# klbr4breakout.net
KiCad netlist of a schematic drawn in EAGLE
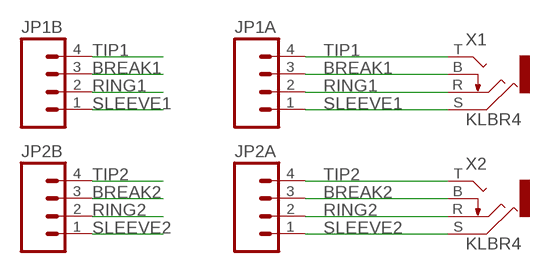
[diagram p0: schematic, sheet 1]

(export (version "E")
  (design (tool "Eeschema 10.0.6"))
  (components
    (comp (ref "JP1A")
      (value "M04PTH")
      (footprint "eagle-import:1X04")
      (libsource (lib "eagle-import") (part "M04PTH"))
    )
    (comp (ref "JP1B")
      (value "M04PTH")
      (footprint "eagle-import:1X04")
      (libsource (lib "eagle-import") (part "M04PTH"))
    )
    (comp (ref "JP2A")
      (value "M04PTH")
      (footprint "eagle-import:1X04")
      (libsource (lib "eagle-import") (part "M04PTH"))
    )
    (comp (ref "JP2B")
      (value "M04PTH")
      (footprint "eagle-import:1X04")
      (libsource (lib "eagle-import") (part "M04PTH"))
    )
    (comp (ref "X1")
      (value "KLBR4")
      (footprint "eagle-import:KLBR4")
      (libsource (lib "eagle-import") (part "KLBR4"))
    )
    (comp (ref "X2")
      (value "KLBR4")
      (footprint "eagle-import:KLBR4")
      (libsource (lib "eagle-import") (part "KLBR4"))
    )
  )
  (nets
    (net (code "1") (name "/BREAK1") (class "Default")
      (node (ref "JP1A") (pin "3") (pinfunction "3_3") (pintype "passive"))
      (node (ref "JP1B") (pin "3") (pinfunction "3_3") (pintype "passive"))
      (node (ref "X1") (pin "B") (pinfunction "B_B") (pintype "passive"))
    )
    (net (code "2") (name "/BREAK2") (class "Default")
      (node (ref "JP2A") (pin "3") (pinfunction "3_3") (pintype "passive"))
      (node (ref "JP2B") (pin "3") (pinfunction "3_3") (pintype "passive"))
      (node (ref "X2") (pin "B") (pinfunction "B_B") (pintype "passive"))
    )
    (net (code "3") (name "/RING1") (class "Default")
      (node (ref "JP1A") (pin "2") (pinfunction "2_2") (pintype "passive"))
      (node (ref "JP1B") (pin "2") (pinfunction "2_2") (pintype "passive"))
      (node (ref "X1") (pin "R") (pinfunction "R_R") (pintype "passive"))
    )
    (net (code "4") (name "/RING2") (class "Default")
      (node (ref "JP2A") (pin "2") (pinfunction "2_2") (pintype "passive"))
      (node (ref "JP2B") (pin "2") (pinfunction "2_2") (pintype "passive"))
      (node (ref "X2") (pin "R") (pinfunction "R_R") (pintype "passive"))
    )
    (net (code "5") (name "/SLEEVE1") (class "Default")
      (node (ref "JP1A") (pin "1") (pinfunction "1_1") (pintype "passive"))
      (node (ref "JP1B") (pin "1") (pinfunction "1_1") (pintype "passive"))
      (node (ref "X1") (pin "S") (pinfunction "S_S") (pintype "passive"))
    )
    (net (code "6") (name "/SLEEVE2") (class "Default")
      (node (ref "JP2A") (pin "1") (pinfunction "1_1") (pintype "passive"))
      (node (ref "JP2B") (pin "1") (pinfunction "1_1") (pintype "passive"))
      (node (ref "X2") (pin "S") (pinfunction "S_S") (pintype "passive"))
    )
    (net (code "7") (name "/TIP1") (class "Default")
      (node (ref "JP1A") (pin "4") (pinfunction "4_4") (pintype "passive"))
      (node (ref "JP1B") (pin "4") (pinfunction "4_4") (pintype "passive"))
      (node (ref "X1") (pin "T") (pinfunction "T_T") (pintype "passive"))
    )
    (net (code "8") (name "/TIP2") (class "Default")
      (node (ref "JP2A") (pin "4") (pinfunction "4_4") (pintype "passive"))
      (node (ref "JP2B") (pin "4") (pinfunction "4_4") (pintype "passive"))
      (node (ref "X2") (pin "T") (pinfunction "T_T") (pintype "passive"))
    )
  )
)
